# servo.net
KiCad netlist of a schematic drawn in Altium Designer
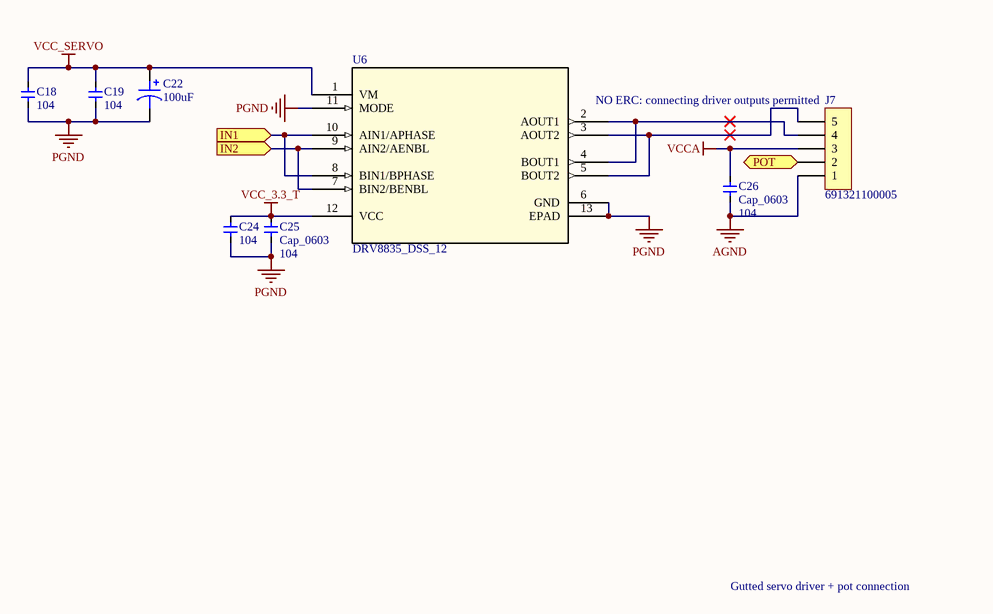
[diagram p0: servo.SchDoc]

(export (version "E")
  (design (tool "Eeschema 10.0.6"))
  (components
    (comp (ref "C18")
      (value "104")
      (footprint "PCB_PassiveCap:CAP_0603")
      (description "Capacitor")
      (fields (field (name "Comment") "Cap_0603"))
      (libsource (lib "SCH_Passive") (part "Cap_0603"))
    )
    (comp (ref "C19")
      (value "104")
      (footprint "PCB_PassiveCap:CAP_0603")
      (description "Capacitor")
      (fields (field (name "Comment") "Cap_0603"))
      (libsource (lib "SCH_Passive") (part "Cap_0603"))
    )
    (comp (ref "C22")
      (value "100uF")
      (footprint "CAP ALUM 6.6MM")
      (description "PCE4180CT-ND")
      (libsource (lib "Passives") (part "Polarised Capacitor"))
    )
    (comp (ref "C24")
      (value "104")
      (footprint "PCB_PassiveCap:CAP_0603")
      (description "Capacitor")
      (fields (field (name "Comment") "Cap_0603"))
      (libsource (lib "SCH_Passive") (part "Cap_0603"))
    )
    (comp (ref "C25")
      (value "Cap_0603")
      (footprint "PCB_PassiveCap:CAP_0603")
      (description "Capacitor")
      (fields (field (name "ALTIUM_VALUE") "104"))
      (libsource (lib "SCH_Passive") (part "Cap_0603"))
    )
    (comp (ref "C26")
      (value "Cap_0603")
      (footprint "PCB_PassiveCap:CAP_0603")
      (description "Capacitor")
      (fields (field (name "ALTIUM_VALUE") "104"))
      (libsource (lib "SCH_Passive") (part "Cap_0603"))
    )
    (comp (ref "J7")
      (value "691321100005")
      (footprint "691322110005")
      (description "WR-TBL Terminal block - serie 3211 - 3.50 mm")
      (fields
        (field (name "MANUFACTURER") "Würth Elektronik eiSos GmbH")
        (field (name "CREATED BY") "Karrer Zheng")
      )
      (libsource (lib "ALTIUM-TBL_3_50_3211_VERTICAL_PCB_HEADER_69132110000X-rev15c") (part "691321100005"))
    )
    (comp (ref "U6")
      (value "DRV8835_DSS_12")
      (footprint "DSS12_P9X2")
      (description "Imported")
      (fields (field (name "MANUFACTURER_PART_NUMBER") "drv8835_dss_12"))
      (libsource (lib "2016-12-05_23-40-09") (part "DRV8835_DSS_12"))
    )
  )
  (nets
    (net (code "1") (name "/IN1") (class "Default")
      (node (ref "U6") (pin "10") (pinfunction "AIN1/APHASE_10") (pintype "input"))
      (node (ref "U6") (pin "8") (pinfunction "BIN1/BPHASE_8") (pintype "input"))
    )
    (net (code "2") (name "/IN2") (class "Default")
      (node (ref "U6") (pin "7") (pinfunction "BIN2/BENBL_7") (pintype "input"))
      (node (ref "U6") (pin "9") (pinfunction "AIN2/AENBL_9") (pintype "input"))
    )
    (net (code "3") (name "/POT") (class "Default")
      (node (ref "J7") (pin "2") (pinfunction "2_2") (pintype "passive"))
    )
    (net (code "4") (name "AGND") (class "Default")
      (node (ref "C26") (pin "2") (pinfunction "2_2") (pintype "passive"))
      (node (ref "J7") (pin "1") (pinfunction "1_1") (pintype "passive"))
    )
    (net (code "5") (name "Net-(U6-AOUT1)") (class "Default")
      (node (ref "J7") (pin "4") (pinfunction "4_4") (pintype "passive"))
      (node (ref "U6") (pin "2") (pinfunction "AOUT1_2") (pintype "output"))
      (node (ref "U6") (pin "4") (pinfunction "BOUT1_4") (pintype "output"))
    )
    (net (code "6") (name "Net-(U6-AOUT2)") (class "Default")
      (node (ref "J7") (pin "5") (pinfunction "5_5") (pintype "passive"))
      (node (ref "U6") (pin "3") (pinfunction "AOUT2_3") (pintype "output"))
      (node (ref "U6") (pin "5") (pinfunction "BOUT2_5") (pintype "output"))
    )
    (net (code "7") (name "PGND") (class "Default")
      (node (ref "C18") (pin "1") (pinfunction "1_1") (pintype "passive"))
      (node (ref "C19") (pin "1") (pinfunction "1_1") (pintype "passive"))
      (node (ref "C22") (pin "2") (pinfunction "2_2") (pintype "passive"))
      (node (ref "C24") (pin "1") (pinfunction "1_1") (pintype "passive"))
      (node (ref "C25") (pin "2") (pinfunction "2_2") (pintype "passive"))
      (node (ref "U6") (pin "11") (pinfunction "MODE_11") (pintype "input"))
      (node (ref "U6") (pin "13") (pinfunction "EPAD_13") (pintype "passive"))
      (node (ref "U6") (pin "6") (pinfunction "GND_6") (pintype "power_in"))
    )
    (net (code "8") (name "VCCA") (class "Default")
      (node (ref "C26") (pin "1") (pinfunction "1_1") (pintype "passive"))
      (node (ref "J7") (pin "3") (pinfunction "3_3") (pintype "passive"))
    )
    (net (code "9") (name "VCC_3.3_T") (class "Default")
      (node (ref "C24") (pin "2") (pinfunction "2_2") (pintype "passive"))
      (node (ref "C25") (pin "1") (pinfunction "1_1") (pintype "passive"))
      (node (ref "U6") (pin "12") (pinfunction "VCC_12") (pintype "power_in"))
    )
    (net (code "10") (name "VCC_SERVO") (class "Default")
      (node (ref "C18") (pin "2") (pinfunction "2_2") (pintype "passive"))
      (node (ref "C19") (pin "2") (pinfunction "2_2") (pintype "passive"))
      (node (ref "C22") (pin "1") (pinfunction "1_1") (pintype "passive"))
      (node (ref "U6") (pin "1") (pinfunction "VM_1") (pintype "power_in"))
    )
  )
)
